# 07_Programming_Reset.net
KiCad netlist of a schematic drawn in Altium Designer
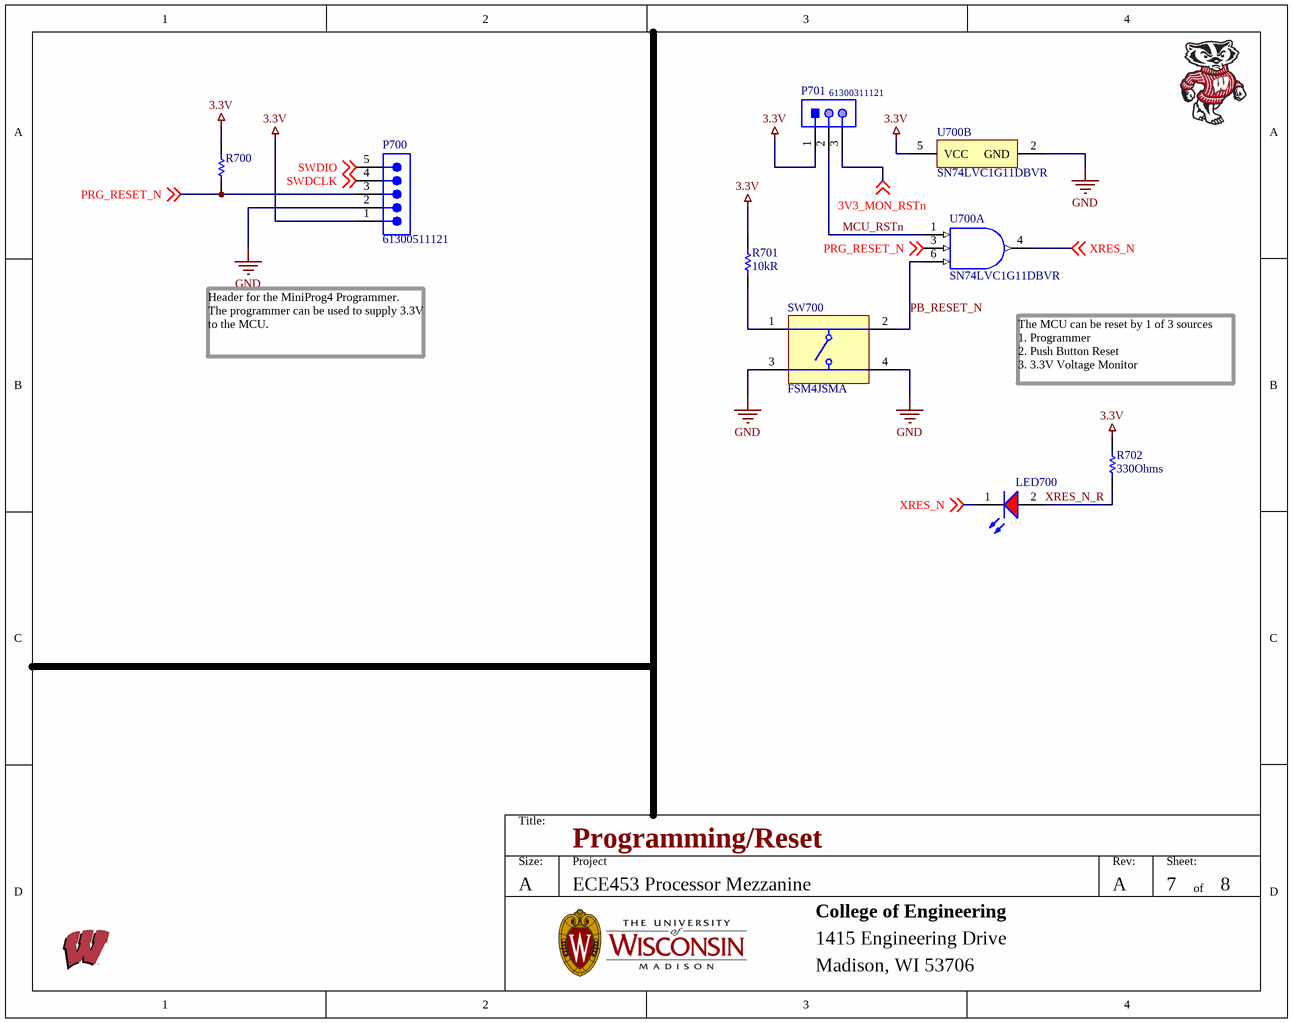
[diagram p0: 07_Programming_Reset.SchDoc]

(export (version "E")
  (design (tool "Eeschema 10.0.6"))
  (components
    (comp (ref "LED700")
      (value "150080RS75000")
      (footprint "WL-SMCW_0805_150080xx75000")
      (libsource (lib "Altium Content Vault") (part "LED_Red_2A-1K"))
    )
    (comp (ref "P700")
      (value "61300511121")
      (footprint "61300511121")
      (libsource (lib "Altium Content Vault") (part "Header_Male_1R_05P"))
    )
    (comp (ref "P701")
      (value "61300311121")
      (footprint "61300311121")
      (description "THT Vertical Pin Header WR-PHD, Pitch 2.54 mm, Single Row, 3 pins")
      (fields (field (name "MANUFACTURER") "Wurth Elektronik") (field (name "PUBLISHER") "WurthElektronik"))
      (libsource (lib "ECE453") (part "CMP-1502-01062-1"))
    )
    (comp (ref "R700")
      (value "RC0805FR-0710KL")
      (footprint "RESC2013X60X35NL10T20")
      (description "Chip Resistor, 10 KOhm, +/- 1%, 0.125 W, -55 to 155 degC, 0805 (2012 Metric), RoHS, Tape and Reel")
      (fields (field (name "MANUFACTURER") "Yageo"))
      (libsource (lib "Altium Content Vault") (part "RES-2"))
    )
    (comp (ref "R701")
      (value "RC0805FR-0710KL")
      (footprint "RESC2013X60X35NL10T20")
      (description "Chip Resistor, 10 KOhm, +/- 1%, 0.125 W, -55 to 155 degC, 0805 (2012 Metric), RoHS, Tape and Reel")
      (fields
        (field (name "MANUFACTURER") "Yageo")
        (field (name "TOLERANCE") "1%")
        (field (name "RESISTANCE") "10kR")
      )
      (libsource (lib "ECE453") (part "CMP-1659-00013-4"))
    )
    (comp (ref "R702")
      (value "RC0805FR-07330RL")
      (footprint "RESC2013X60X35LL10T20")
      (description "Chip Resistor, 330 Ohm, +/- 1%, 125 mW, -55 to 155 degC, 0805 (2012 Metric), RoHS, Tape and Reel")
      (fields
        (field (name "MANUFACTURER") "Yageo")
        (field (name "TOLERANCE") "1%")
        (field (name "RESISTANCE") "330Ohms")
      )
      (libsource (lib "Altium Content Vault") (part "RES-2"))
    )
    (comp (ref "SW700")
      (value "FSM4JSMA")
      (footprint "TECO-FSM4JSMA_V")
      (description "Swicth, SPST, 24 V, -35 to 85 degC, 4-Pin SMD, RoHS, Tape and Reel")
      (fields (field (name "MANUFACTURER") "TE Connectivity"))
      (libsource (lib "ECE453") (part "CMP-2000-05602-2"))
    )
    (comp (ref "U700")
      (value "SN74LVC1G11DBVR")
      (footprint "DBV0006A_N")
      (description "Single 3-Input Positive-AND Gate, DBV0006A, LARGE T&R")
      (fields
        (field (name "MANUFACTURER") "Texas Instruments")
        (field (name "GENERIC PART NUMBER") "SN74LVC1G11")
      )
      (libsource (lib "Altium Content Vault") (part "TI-AND-1-3IN-6"))
    )
  )
  (nets
    (net (code "1") (name "/MCU_RSTn") (class "Default")
      (node (ref "P701") (pin "2") (pinfunction "2_2") (pintype "passive"))
      (node (ref "U700") (pin "1") (pinfunction "A_1") (pintype "input"))
    )
    (net (code "2") (name "/PB_RESET_N") (class "Default")
      (node (ref "SW700") (pin "2") (pinfunction "2_2") (pintype "passive"))
      (node (ref "U700") (pin "6") (pinfunction "C_6") (pintype "input"))
    )
    (net (code "3") (name "/XRES_N_R") (class "Default")
      (node (ref "LED700") (pin "2") (pinfunction "A_2") (pintype "passive"))
      (node (ref "R702") (pin "1") (pinfunction "1_1") (pintype "passive"))
    )
    (net (code "4") (name "3.3V") (class "Default")
      (node (ref "P700") (pin "1") (pinfunction "1_1") (pintype "passive"))
      (node (ref "P701") (pin "1") (pinfunction "1_1") (pintype "passive"))
      (node (ref "R700") (pin "2") (pinfunction "2_2") (pintype "passive"))
      (node (ref "R701") (pin "2") (pinfunction "2_2") (pintype "passive"))
      (node (ref "R702") (pin "2") (pinfunction "2_2") (pintype "passive"))
      (node (ref "U700") (pin "5") (pinfunction "VCC_5") (pintype "power_in"))
    )
    (net (code "5") (name "3V3_MON_RSTn") (class "Default")
      (node (ref "P701") (pin "3") (pinfunction "3_3") (pintype "passive"))
    )
    (net (code "6") (name "GND") (class "Default")
      (node (ref "P700") (pin "2") (pinfunction "2_2") (pintype "passive"))
      (node (ref "SW700") (pin "3") (pinfunction "3_3") (pintype "passive"))
      (node (ref "SW700") (pin "4") (pinfunction "4_4") (pintype "passive"))
      (node (ref "U700") (pin "2") (pinfunction "GND_2") (pintype "power_in"))
    )
    (net (code "7") (name "Net-(R701-Pad1)") (class "Default")
      (node (ref "R701") (pin "1") (pinfunction "1_1") (pintype "passive"))
      (node (ref "SW700") (pin "1") (pinfunction "1_1") (pintype "passive"))
    )
    (net (code "8") (name "PRG_RESET_N") (class "Default")
      (node (ref "P700") (pin "3") (pinfunction "3_3") (pintype "passive"))
      (node (ref "R700") (pin "1") (pinfunction "1_1") (pintype "passive"))
      (node (ref "U700") (pin "3") (pinfunction "B_3") (pintype "input"))
    )
    (net (code "9") (name "SWDCLK") (class "Default")
      (node (ref "P700") (pin "4") (pinfunction "4_4") (pintype "passive"))
    )
    (net (code "10") (name "SWDIO") (class "Default")
      (node (ref "P700") (pin "5") (pinfunction "5_5") (pintype "passive"))
    )
    (net (code "11") (name "XRES_N") (class "Default")
      (node (ref "LED700") (pin "1") (pinfunction "K_1") (pintype "passive"))
      (node (ref "U700") (pin "4") (pinfunction "Y_4") (pintype "output"))
    )
  )
)
